# Carga_util_v2.net
KiCad netlist of a schematic drawn in Altium Designer
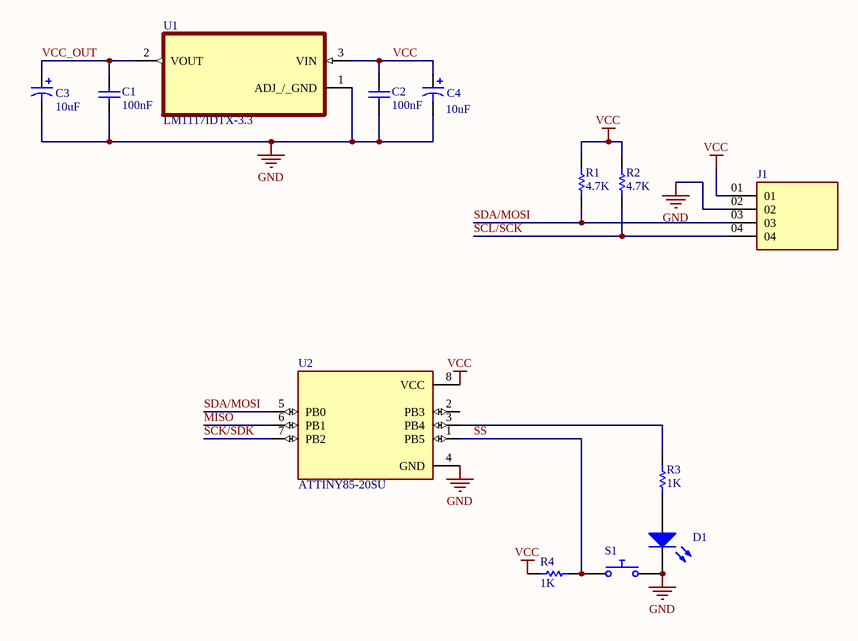
[diagram p0: Carga_util_v2.SchDoc]

(export (version "E")
  (design (tool "Eeschema 10.0.6"))
  (components
    (comp (ref "C1")
      (value "100nF")
      (description "Capacitor")
      (libsource (lib "Simulation Generic Components") (part "Capacitor"))
    )
    (comp (ref "C2")
      (value "100nF")
      (description "Capacitor")
      (libsource (lib "Simulation Generic Components") (part "Capacitor"))
    )
    (comp (ref "C3")
      (value "10uF")
      (footprint "RB7.6-15")
      (description "Polarized Capacitor (Radial)")
      (fields (field (name "Comment") "Cap Pol1") (field (name "PUBLISHER") "Altium Limited"))
      (libsource (lib "Miscellaneous Devices") (part "Cap Pol1"))
    )
    (comp (ref "C4")
      (value "10uF")
      (footprint "RB7.6-15")
      (description "Polarized Capacitor (Radial)")
      (fields (field (name "Comment") "Cap Pol1") (field (name "PUBLISHER") "Altium Limited"))
      (libsource (lib "Miscellaneous Devices") (part "Cap Pol1"))
    )
    (comp (ref "D1")
      (value "Light-Emitting Diode")
      (libsource (lib "Simulation Generic Components") (part "LED"))
    )
    (comp (ref "J1")
      (value "TSW-104-07-T-S-LL")
      (footprint "SAMTEC_TSW-104-07-T-S-LL")
      (libsource (lib "TSW-104-07-T-S-LL") (part "TSW-104-07-T-S-LL"))
    )
    (comp (ref "R1")
      (value "4.7K")
      (description "Resistor")
      (libsource (lib "Simulation Generic Components") (part "Resistor"))
    )
    (comp (ref "R2")
      (value "4.7K")
      (description "Resistor")
      (libsource (lib "Simulation Generic Components") (part "Resistor"))
    )
    (comp (ref "R3")
      (value "1K")
      (description "Resistor")
      (libsource (lib "Simulation Generic Components") (part "Resistor"))
    )
    (comp (ref "R4")
      (value "1K")
      (description "Resistor")
      (libsource (lib "Simulation Generic Components") (part "Resistor"))
    )
    (comp (ref "S1")
      (value "Push Button Normally Opened")
      (libsource (lib "Simulation Generic Components") (part "Push Button NO"))
    )
    (comp (ref "U1")
      (value "LM1117IDTX-3.3")
      (footprint "TO228P970X238-3N:TO228P970X238-3N")
      (description "Linear Voltage Regulator IC 1 Output 800mA TO-252-3")
      (fields
        (field (name "MF") "Texas Instruments")
        (field (name "DIGI-KEY_PART_NUMBER") "LM1117IDTX-3.3/NOPBCT-ND")
      )
      (libsource (lib "LM1117IDTX-3.3") (part "LM1117IDTX-3.3"))
    )
    (comp (ref "U2")
      (value "ATTINY85-20SU")
      (footprint "SOIC127P798X216-8N")
      (fields (field (name "MF") "Microchip Technology"))
      (libsource (lib "ATTINY85-20SU") (part "ATTINY85-20SU"))
    )
  )
  (nets
    (net (code "1") (name "/MISO") (class "Default")
      (node (ref "U2") (pin "6") (pinfunction "PB1_6") (pintype "bidirectional"))
    )
    (net (code "2") (name "/SCK{slash}SDK") (class "Default")
      (node (ref "U2") (pin "7") (pinfunction "PB2_7") (pintype "bidirectional"))
    )
    (net (code "3") (name "/SCL{slash}SCK") (class "Default")
      (node (ref "J1") (pin "04") (pinfunction "04_04") (pintype "passive"))
      (node (ref "R2") (pin "1") (pinfunction "1_1") (pintype "passive"))
    )
    (net (code "4") (name "/SDA{slash}MOSI") (class "Default")
      (node (ref "J1") (pin "03") (pinfunction "03_03") (pintype "passive"))
      (node (ref "R1") (pin "1") (pinfunction "1_1") (pintype "passive"))
      (node (ref "U2") (pin "5") (pinfunction "PB0_5") (pintype "bidirectional"))
    )
    (net (code "5") (name "/SS") (class "Default")
      (node (ref "R4") (pin "2") (pinfunction "2_2") (pintype "passive"))
      (node (ref "S1") (pin "1") (pinfunction "1_1") (pintype "passive"))
      (node (ref "U2") (pin "1") (pinfunction "PB5_1") (pintype "bidirectional"))
    )
    (net (code "6") (name "/VCC_OUT") (class "Default")
      (node (ref "C1") (pin "2") (pinfunction "2_2") (pintype "passive"))
      (node (ref "C3") (pin "1") (pinfunction "1_1") (pintype "passive"))
      (node (ref "U1") (pin "2") (pinfunction "VOUT_2") (pintype "output"))
    )
    (net (code "7") (name "GND") (class "Default")
      (node (ref "C1") (pin "1") (pinfunction "1_1") (pintype "passive"))
      (node (ref "C2") (pin "1") (pinfunction "1_1") (pintype "passive"))
      (node (ref "C3") (pin "2") (pinfunction "2_2") (pintype "passive"))
      (node (ref "C4") (pin "2") (pinfunction "2_2") (pintype "passive"))
      (node (ref "D1") (pin "2") (pinfunction "K_2") (pintype "passive"))
      (node (ref "J1") (pin "02") (pinfunction "02_02") (pintype "passive"))
      (node (ref "S1") (pin "2") (pinfunction "2_2") (pintype "passive"))
      (node (ref "U1") (pin "1") (pinfunction "ADJ_/_GND_1") (pintype "power_in"))
      (node (ref "U2") (pin "4") (pinfunction "GND_4") (pintype "power_in"))
    )
    (net (code "8") (name "Net-(D1-A)") (class "Default")
      (node (ref "D1") (pin "1") (pinfunction "A_1") (pintype "passive"))
      (node (ref "R3") (pin "1") (pinfunction "1_1") (pintype "passive"))
    )
    (net (code "9") (name "Net-(U2-PB4)") (class "Default")
      (node (ref "R3") (pin "2") (pinfunction "2_2") (pintype "passive"))
      (node (ref "U2") (pin "3") (pinfunction "PB4_3") (pintype "bidirectional"))
    )
    (net (code "10") (name "VCC") (class "Default")
      (node (ref "C2") (pin "2") (pinfunction "2_2") (pintype "passive"))
      (node (ref "C4") (pin "1") (pinfunction "1_1") (pintype "passive"))
      (node (ref "J1") (pin "01") (pinfunction "01_01") (pintype "passive"))
      (node (ref "R1") (pin "2") (pinfunction "2_2") (pintype "passive"))
      (node (ref "R2") (pin "2") (pinfunction "2_2") (pintype "passive"))
      (node (ref "R4") (pin "1") (pinfunction "1_1") (pintype "passive"))
      (node (ref "U1") (pin "3") (pinfunction "VIN_3") (pintype "input"))
      (node (ref "U2") (pin "8") (pinfunction "VCC_8") (pintype "power_in"))
    )
    (net (code "11") (name "unconnected-(U2-PB3-Pad2)") (class "Default")
      (node (ref "U2") (pin "2") (pinfunction "PB3_2") (pintype "bidirectional"))
    )
  )
)
